# Sheet1.net
KiCad netlist of a schematic drawn in Altium Designer
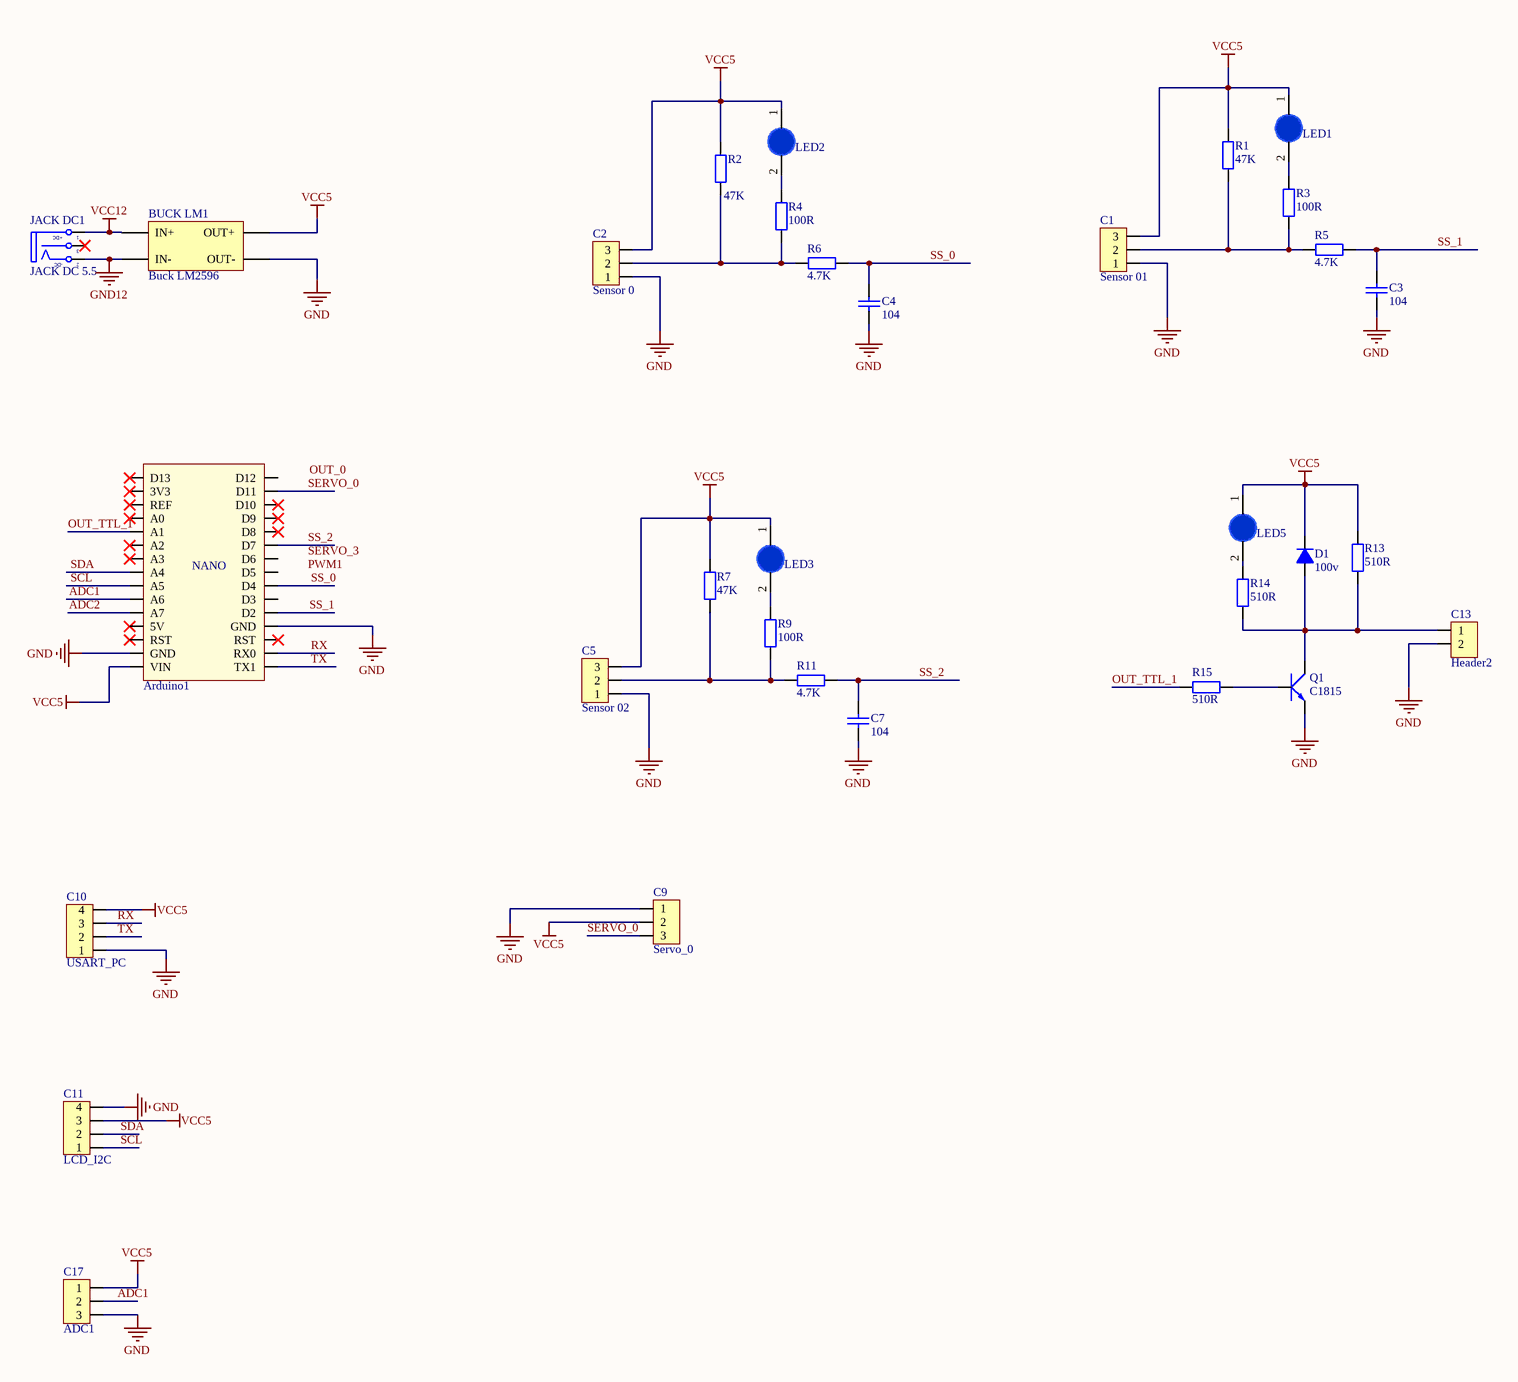
[diagram p0: Sheet1.SchDoc]

(export (version "E")
  (design (tool "Eeschema 10.0.6"))
  (components
    (comp (ref "Arduino1")
      (value "Arduino Nano")
      (footprint "Arduino Nano")
      (description "Arduino NANO")
      (libsource (lib "myLib_v1") (part "Arduino Nano"))
    )
    (comp (ref "BUCK LM1")
      (value "Buck LM2596")
      (footprint "BUCK LM2596")
      (libsource (lib "myLib_v1") (part "Buck LM2596"))
    )
    (comp (ref "C1")
      (value "Sensor 01")
      (footprint "Header3")
      (description "Header IDC, 3 x 1 Pin Vertical 2.54mm Pitch (Non-Boxed, Male)")
      (fields
        (field (name "MANUFACTURER") "Würth Elektronik eiSos GmbH")
        (field (name "PARTNO") "613002143121")
        (field (name "CREATED BY") "Karrer Zheng")
      )
      (libsource (lib "myLib_v1") (part "Header3"))
    )
    (comp (ref "C2")
      (value "Sensor 0")
      (footprint "Header3")
      (description "Header IDC, 3 x 1 Pin Vertical 2.54mm Pitch (Non-Boxed, Male)")
      (fields
        (field (name "MANUFACTURER") "Würth Elektronik eiSos GmbH")
        (field (name "PARTNO") "613002143121")
        (field (name "CREATED BY") "Karrer Zheng")
      )
      (libsource (lib "myLib_v1") (part "Header3"))
    )
    (comp (ref "C3")
      (value "104")
      (footprint "tu gom")
      (description "Cắm")
      (libsource (lib "Altium_Lib_by_KhueNguyenCreator") (part "Tu gom 104 50V"))
    )
    (comp (ref "C4")
      (value "104")
      (footprint "tu gom")
      (description "Cắm")
      (libsource (lib "Altium_Lib_by_KhueNguyenCreator") (part "Tu gom 104 50V"))
    )
    (comp (ref "C5")
      (value "Sensor 02")
      (footprint "Header3")
      (description "Header IDC, 3 x 1 Pin Vertical 2.54mm Pitch (Non-Boxed, Male)")
      (fields
        (field (name "MANUFACTURER") "Würth Elektronik eiSos GmbH")
        (field (name "PARTNO") "613002143121")
        (field (name "CREATED BY") "Karrer Zheng")
      )
      (libsource (lib "myLib_v1") (part "Header3"))
    )
    (comp (ref "C7")
      (value "104")
      (footprint "tu gom")
      (description "Cắm")
      (libsource (lib "Altium_Lib_by_KhueNguyenCreator") (part "Tu gom 104 50V"))
    )
    (comp (ref "C9")
      (value "Servo_0")
      (footprint "Header3")
      (description "Header IDC, 3 x 1 Pin Vertical 2.54mm Pitch (Non-Boxed, Male)")
      (fields
        (field (name "MANUFACTURER") "Würth Elektronik eiSos GmbH")
        (field (name "PARTNO") "613002143121")
        (field (name "CREATED BY") "Karrer Zheng")
      )
      (libsource (lib "") (part "Header3_1"))
    )
    (comp (ref "C10")
      (value "USART_PC")
      (footprint "Header4")
      (description "Header IDC, 4 x 1 Pin Vertical 2.54mm Pitch (Non-Boxed, Male)")
      (fields
        (field (name "MANUFACTURER") "Würth Elektronik eiSos GmbH")
        (field (name "PARTNO") "613002143121")
        (field (name "CREATED BY") "Karrer Zheng")
      )
      (libsource (lib "myLib_v1") (part "Header4"))
    )
    (comp (ref "C11")
      (value "LCD_I2C")
      (footprint "Header4")
      (description "Header IDC, 4 x 1 Pin Vertical 2.54mm Pitch (Non-Boxed, Male)")
      (fields
        (field (name "MANUFACTURER") "Würth Elektronik eiSos GmbH")
        (field (name "PARTNO") "613002143121")
        (field (name "CREATED BY") "Karrer Zheng")
      )
      (libsource (lib "myLib_v1") (part "Header4"))
    )
    (comp (ref "C13")
      (value "Header2")
      (footprint "Header2")
      (description "Header IDC, 2 x 1 Pin Vertical 2.54mm Pitch (Non-Boxed, Male)")
      (fields
        (field (name "MANUFACTURER") "Würth Elektronik eiSos GmbH")
        (field (name "PARTNO") "613002143121")
        (field (name "CREATED BY") "Karrer Zheng")
      )
      (libsource (lib "myLib_v1") (part "Header2"))
    )
    (comp (ref "C17")
      (value "ADC1")
      (footprint "Header3")
      (description "Header IDC, 3 x 1 Pin Vertical 2.54mm Pitch (Non-Boxed, Male)")
      (fields
        (field (name "MANUFACTURER") "Würth Elektronik eiSos GmbH")
        (field (name "PARTNO") "613002143121")
        (field (name "CREATED BY") "Karrer Zheng")
      )
      (libsource (lib "") (part "Header3_2"))
    )
    (comp (ref "D1")
      (value "100v")
      (footprint "DIODE 0.5A")
      (description "Cắm")
      (libsource (lib "Altium_Lib_by_KhueNguyenCreator") (part "Diode 1N4148"))
    )
    (comp (ref "JACK DC1")
      (value "JACK DC 5.5")
      (footprint "JACK DC 5.5")
      (libsource (lib "Altium_Lib_by_KhueNguyenCreator") (part "JACK DC 5.5"))
    )
    (comp (ref "LED1")
      (value "LED 3mm")
      (footprint "LED-3MM-BLUE")
      (description "Cắm")
      (libsource (lib "myLib_v1") (part "LED 3mm Xanh Duong"))
    )
    (comp (ref "LED2")
      (value "LED 3mm")
      (footprint "LED-3MM-BLUE")
      (description "Cắm")
      (libsource (lib "myLib_v1") (part "LED 3mm Xanh Duong"))
    )
    (comp (ref "LED3")
      (value "LED 3mm")
      (footprint "LED-3MM-BLUE")
      (description "Cắm")
      (libsource (lib "myLib_v1") (part "LED 3mm Xanh Duong"))
    )
    (comp (ref "LED5")
      (value "LED 3mm")
      (footprint "LED-3MM-BLUE")
      (description "Cắm")
      (libsource (lib "myLib_v1") (part "LED 3mm Xanh Duong"))
    )
    (comp (ref "Q1")
      (value "C1815")
      (footprint "C1815_cam")
      (description "NPN 600mW, ECB")
      (libsource (lib "myLib_v1") (part "C1815"))
    )
    (comp (ref "R1")
      (value "47K")
      (footprint "R1/4W")
      (description "Resistor 1/4W")
      (libsource (lib "myLib_v1") (part "R1/4W"))
    )
    (comp (ref "R2")
      (value "47K")
      (footprint "R1/4W")
      (description "Resistor 1/4W")
      (libsource (lib "myLib_v1") (part "R1/4W"))
    )
    (comp (ref "R3")
      (value "100R")
      (footprint "R1/4W")
      (description "Resistor 1/4W")
      (libsource (lib "myLib_v1") (part "R1/4W"))
    )
    (comp (ref "R4")
      (value "100R")
      (footprint "R1/4W")
      (description "Resistor 1/4W")
      (libsource (lib "myLib_v1") (part "R1/4W"))
    )
    (comp (ref "R5")
      (value "4.7K")
      (footprint "R1/4W")
      (description "Resistor 1/4W")
      (libsource (lib "myLib_v1") (part "R1/4W"))
    )
    (comp (ref "R6")
      (value "4.7K")
      (footprint "R1/4W")
      (description "Resistor 1/4W")
      (libsource (lib "myLib_v1") (part "R1/4W"))
    )
    (comp (ref "R7")
      (value "47K")
      (footprint "R1/4W")
      (description "Resistor 1/4W")
      (libsource (lib "myLib_v1") (part "R1/4W"))
    )
    (comp (ref "R9")
      (value "100R")
      (footprint "R1/4W")
      (description "Resistor 1/4W")
      (libsource (lib "myLib_v1") (part "R1/4W"))
    )
    (comp (ref "R11")
      (value "4.7K")
      (footprint "R1/4W")
      (description "Resistor 1/4W")
      (libsource (lib "myLib_v1") (part "R1/4W"))
    )
    (comp (ref "R13")
      (value "510R")
      (footprint "R1/4W")
      (description "Resistor 1/4W")
      (libsource (lib "myLib_v1") (part "R1/4W"))
    )
    (comp (ref "R14")
      (value "510R")
      (footprint "R1/4W")
      (description "Resistor 1/4W")
      (libsource (lib "myLib_v1") (part "R1/4W"))
    )
    (comp (ref "R15")
      (value "510R")
      (footprint "R1/4W")
      (description "Resistor 1/4W")
      (libsource (lib "myLib_v1") (part "R1/4W"))
    )
  )
  (nets
    (net (code "1") (name "/ADC1") (class "Default")
      (node (ref "Arduino1") (pin "A6") (pinfunction "A6_A6") (pintype "passive"))
      (node (ref "C17") (pin "2") (pinfunction "2_2") (pintype "passive"))
    )
    (net (code "2") (name "/ADC2") (class "Default")
      (node (ref "Arduino1") (pin "A7") (pinfunction "A7_A7") (pintype "passive"))
    )
    (net (code "4") (name "/OUT_TTL_1") (class "Default")
      (node (ref "Arduino1") (pin "A1") (pinfunction "A1_A1") (pintype "passive"))
      (node (ref "R15") (pin "1") (pinfunction "1_1") (pintype "passive"))
    )
    (net (code "6") (name "/RX") (class "Default")
      (node (ref "Arduino1") (pin "RX0") (pinfunction "RX0_RX0") (pintype "passive"))
      (node (ref "C10") (pin "3") (pinfunction "3_3") (pintype "passive"))
    )
    (net (code "7") (name "/SCL") (class "Default")
      (node (ref "Arduino1") (pin "A5") (pinfunction "A5_A5") (pintype "passive"))
      (node (ref "C11") (pin "1") (pinfunction "1_1") (pintype "passive"))
    )
    (net (code "8") (name "/SDA") (class "Default")
      (node (ref "Arduino1") (pin "A4") (pinfunction "A4_A4") (pintype "passive"))
      (node (ref "C11") (pin "2") (pinfunction "2_2") (pintype "passive"))
    )
    (net (code "9") (name "/SERVO_0") (class "Default")
      (node (ref "Arduino1") (pin "D11") (pinfunction "D11_D11") (pintype "passive"))
      (node (ref "C9") (pin "3") (pinfunction "3_3") (pintype "passive"))
    )
    (net (code "11") (name "/SS_0") (class "Default")
      (node (ref "Arduino1") (pin "D4") (pinfunction "D4_D4") (pintype "passive"))
      (node (ref "C4") (pin "1") (pinfunction "1_1") (pintype "passive"))
      (node (ref "R6") (pin "1") (pinfunction "1_1") (pintype "passive"))
    )
    (net (code "12") (name "/SS_1") (class "Default")
      (node (ref "Arduino1") (pin "D2") (pinfunction "D2_D2") (pintype "passive"))
      (node (ref "C3") (pin "1") (pinfunction "1_1") (pintype "passive"))
      (node (ref "R5") (pin "1") (pinfunction "1_1") (pintype "passive"))
    )
    (net (code "13") (name "/SS_2") (class "Default")
      (node (ref "Arduino1") (pin "D7") (pinfunction "D7_D7") (pintype "passive"))
      (node (ref "C7") (pin "1") (pinfunction "1_1") (pintype "passive"))
      (node (ref "R11") (pin "1") (pinfunction "1_1") (pintype "passive"))
    )
    (net (code "14") (name "/TX") (class "Default")
      (node (ref "Arduino1") (pin "TX1") (pinfunction "TX1_TX1") (pintype "passive"))
      (node (ref "C10") (pin "2") (pinfunction "2_2") (pintype "passive"))
    )
    (net (code "15") (name "GND") (class "Default")
      (node (ref "Arduino1") (pin "GND") (pinfunction "GND_GND") (pintype "passive"))
      (node (ref "BUCK LM1") (pin "3") (pinfunction "OUT-_3") (pintype "passive"))
      (node (ref "C1") (pin "1") (pinfunction "1_1") (pintype "passive"))
      (node (ref "C10") (pin "1") (pinfunction "1_1") (pintype "passive"))
      (node (ref "C11") (pin "4") (pinfunction "4_4") (pintype "passive"))
      (node (ref "C13") (pin "2") (pinfunction "2_2") (pintype "passive"))
      (node (ref "C17") (pin "3") (pinfunction "3_3") (pintype "passive"))
      (node (ref "C2") (pin "1") (pinfunction "1_1") (pintype "passive"))
      (node (ref "C3") (pin "2") (pinfunction "2_2") (pintype "passive"))
      (node (ref "C4") (pin "2") (pinfunction "2_2") (pintype "passive"))
      (node (ref "C5") (pin "1") (pinfunction "1_1") (pintype "passive"))
      (node (ref "C7") (pin "2") (pinfunction "2_2") (pintype "passive"))
      (node (ref "C9") (pin "1") (pinfunction "1_1") (pintype "passive"))
      (node (ref "Q1") (pin "1") (pinfunction "E_1") (pintype "passive"))
    )
    (net (code "16") (name "GND12") (class "Default")
      (node (ref "BUCK LM1") (pin "2") (pinfunction "IN-_2") (pintype "passive"))
      (node (ref "JACK DC1") (pin "2") (pinfunction "TN_2") (pintype "passive"))
    )
    (net (code "17") (name "Net-(C1-Pad2)") (class "Default")
      (node (ref "C1") (pin "2") (pinfunction "2_2") (pintype "passive"))
      (node (ref "R1") (pin "1") (pinfunction "1_1") (pintype "passive"))
      (node (ref "R3") (pin "1") (pinfunction "1_1") (pintype "passive"))
      (node (ref "R5") (pin "2") (pinfunction "2_2") (pintype "passive"))
    )
    (net (code "18") (name "Net-(C2-Pad2)") (class "Default")
      (node (ref "C2") (pin "2") (pinfunction "2_2") (pintype "passive"))
      (node (ref "R2") (pin "1") (pinfunction "1_1") (pintype "passive"))
      (node (ref "R4") (pin "1") (pinfunction "1_1") (pintype "passive"))
      (node (ref "R6") (pin "2") (pinfunction "2_2") (pintype "passive"))
    )
    (net (code "19") (name "Net-(C5-Pad2)") (class "Default")
      (node (ref "C5") (pin "2") (pinfunction "2_2") (pintype "passive"))
      (node (ref "R11") (pin "2") (pinfunction "2_2") (pintype "passive"))
      (node (ref "R7") (pin "1") (pinfunction "1_1") (pintype "passive"))
      (node (ref "R9") (pin "1") (pinfunction "1_1") (pintype "passive"))
    )
    (net (code "20") (name "Net-(D1-A)") (class "Default")
      (node (ref "C13") (pin "1") (pinfunction "1_1") (pintype "passive"))
      (node (ref "D1") (pin "1") (pinfunction "A_1") (pintype "passive"))
      (node (ref "Q1") (pin "2") (pinfunction "C_2") (pintype "passive"))
      (node (ref "R13") (pin "2") (pinfunction "2_2") (pintype "passive"))
      (node (ref "R14") (pin "2") (pinfunction "2_2") (pintype "passive"))
    )
    (net (code "21") (name "Net-(LED1-K)") (class "Default")
      (node (ref "LED1") (pin "2") (pinfunction "K_2") (pintype "passive"))
      (node (ref "R3") (pin "2") (pinfunction "2_2") (pintype "passive"))
    )
    (net (code "22") (name "Net-(LED2-K)") (class "Default")
      (node (ref "LED2") (pin "2") (pinfunction "K_2") (pintype "passive"))
      (node (ref "R4") (pin "2") (pinfunction "2_2") (pintype "passive"))
    )
    (net (code "23") (name "Net-(LED3-K)") (class "Default")
      (node (ref "LED3") (pin "2") (pinfunction "K_2") (pintype "passive"))
      (node (ref "R9") (pin "2") (pinfunction "2_2") (pintype "passive"))
    )
    (net (code "24") (name "Net-(LED5-K)") (class "Default")
      (node (ref "LED5") (pin "2") (pinfunction "K_2") (pintype "passive"))
      (node (ref "R14") (pin "1") (pinfunction "1_1") (pintype "passive"))
    )
    (net (code "25") (name "Net-(Q1-B)") (class "Default")
      (node (ref "Q1") (pin "3") (pinfunction "B_3") (pintype "passive"))
      (node (ref "R15") (pin "2") (pinfunction "2_2") (pintype "passive"))
    )
    (net (code "26") (name "VCC5") (class "Default")
      (node (ref "Arduino1") (pin "VIN") (pinfunction "VIN_VIN") (pintype "passive"))
      (node (ref "BUCK LM1") (pin "4") (pinfunction "OUT+_4") (pintype "passive"))
      (node (ref "C1") (pin "3") (pinfunction "3_3") (pintype "passive"))
      (node (ref "C10") (pin "4") (pinfunction "4_4") (pintype "passive"))
      (node (ref "C11") (pin "3") (pinfunction "3_3") (pintype "passive"))
      (node (ref "C17") (pin "1") (pinfunction "1_1") (pintype "passive"))
      (node (ref "C2") (pin "3") (pinfunction "3_3") (pintype "passive"))
      (node (ref "C5") (pin "3") (pinfunction "3_3") (pintype "passive"))
      (node (ref "C9") (pin "2") (pinfunction "2_2") (pintype "passive"))
      (node (ref "D1") (pin "2") (pinfunction "K_2") (pintype "passive"))
      (node (ref "LED1") (pin "1") (pinfunction "A_1") (pintype "passive"))
      (node (ref "LED2") (pin "1") (pinfunction "A_1") (pintype "passive"))
      (node (ref "LED3") (pin "1") (pinfunction "A_1") (pintype "passive"))
      (node (ref "LED5") (pin "1") (pinfunction "A_1") (pintype "passive"))
      (node (ref "R1") (pin "2") (pinfunction "2_2") (pintype "passive"))
      (node (ref "R13") (pin "1") (pinfunction "1_1") (pintype "passive"))
      (node (ref "R2") (pin "2") (pinfunction "2_2") (pintype "passive"))
      (node (ref "R7") (pin "2") (pinfunction "2_2") (pintype "passive"))
    )
    (net (code "27") (name "VCC12") (class "Default")
      (node (ref "BUCK LM1") (pin "1") (pinfunction "IN+_1") (pintype "passive"))
      (node (ref "JACK DC1") (pin "1") (pinfunction "T_1") (pintype "passive"))
    )
    (net (code "28") (name "unconnected-(Arduino1-Pad3V3)") (class "Default")
      (node (ref "Arduino1") (pin "3V3") (pinfunction "3V3_3V3") (pintype "passive+no_connect"))
    )
    (net (code "29") (name "unconnected-(Arduino1-Pad5V)") (class "Default")
      (node (ref "Arduino1") (pin "5V") (pinfunction "5V_5V") (pintype "passive+no_connect"))
    )
    (net (code "30") (name "unconnected-(Arduino1-PadA0)") (class "Default")
      (node (ref "Arduino1") (pin "A0") (pinfunction "A0_A0") (pintype "passive+no_connect"))
    )
    (net (code "31") (name "unconnected-(Arduino1-PadA2)") (class "Default")
      (node (ref "Arduino1") (pin "A2") (pinfunction "A2_A2") (pintype "passive+no_connect"))
    )
    (net (code "32") (name "unconnected-(Arduino1-PadA3)") (class "Default")
      (node (ref "Arduino1") (pin "A3") (pinfunction "A3_A3") (pintype "passive+no_connect"))
    )
    (net (code "33") (name "unconnected-(Arduino1-PadD3)") (class "Default")
      (node (ref "Arduino1") (pin "D3") (pinfunction "D3_D3") (pintype "passive"))
    )
    (net (code "34") (name "unconnected-(Arduino1-PadD5)") (class "Default")
      (node (ref "Arduino1") (pin "D5") (pinfunction "D5_D5") (pintype "passive"))
    )
    (net (code "35") (name "unconnected-(Arduino1-PadD6)") (class "Default")
      (node (ref "Arduino1") (pin "D6") (pinfunction "D6_D6") (pintype "passive"))
    )
    (net (code "36") (name "unconnected-(Arduino1-PadD8)") (class "Default")
      (node (ref "Arduino1") (pin "D8") (pinfunction "D8_D8") (pintype "passive+no_connect"))
    )
    (net (code "37") (name "unconnected-(Arduino1-PadD9)") (class "Default")
      (node (ref "Arduino1") (pin "D9") (pinfunction "D9_D9") (pintype "passive+no_connect"))
    )
    (net (code "38") (name "unconnected-(Arduino1-PadD10)") (class "Default")
      (node (ref "Arduino1") (pin "D10") (pinfunction "D10_D10") (pintype "passive+no_connect"))
    )
    (net (code "39") (name "unconnected-(Arduino1-PadD12)") (class "Default")
      (node (ref "Arduino1") (pin "D12") (pinfunction "D12_D12") (pintype "passive"))
    )
    (net (code "40") (name "unconnected-(Arduino1-PadD13)") (class "Default")
      (node (ref "Arduino1") (pin "D13") (pinfunction "D13_D13") (pintype "passive+no_connect"))
    )
    (net (code "41") (name "unconnected-(Arduino1-PadREF)") (class "Default")
      (node (ref "Arduino1") (pin "REF") (pinfunction "REF_REF") (pintype "passive+no_connect"))
    )
    (net (code "42") (name "unconnected-(Arduino1-PadRST)") (class "Default")
      (node (ref "Arduino1") (pin "RST") (pinfunction "RST_RST") (pintype "passive+no_connect"))
    )
    (net (code "43") (name "unconnected-(Arduino1-PadRST)_1") (class "Default")
      (node (ref "Arduino1") (pin "RST") (pinfunction "RST_RST") (pintype "passive+no_connect"))
    )
    (net (code "44") (name "unconnected-(JACK DC1-S-Pad3)") (class "Default")
      (node (ref "JACK DC1") (pin "3") (pinfunction "S_3") (pintype "power_in+no_connect"))
    )
  )
)
